# gigatron-expansion-v5.net
KiCad netlist of a schematic drawn in EasyEDA
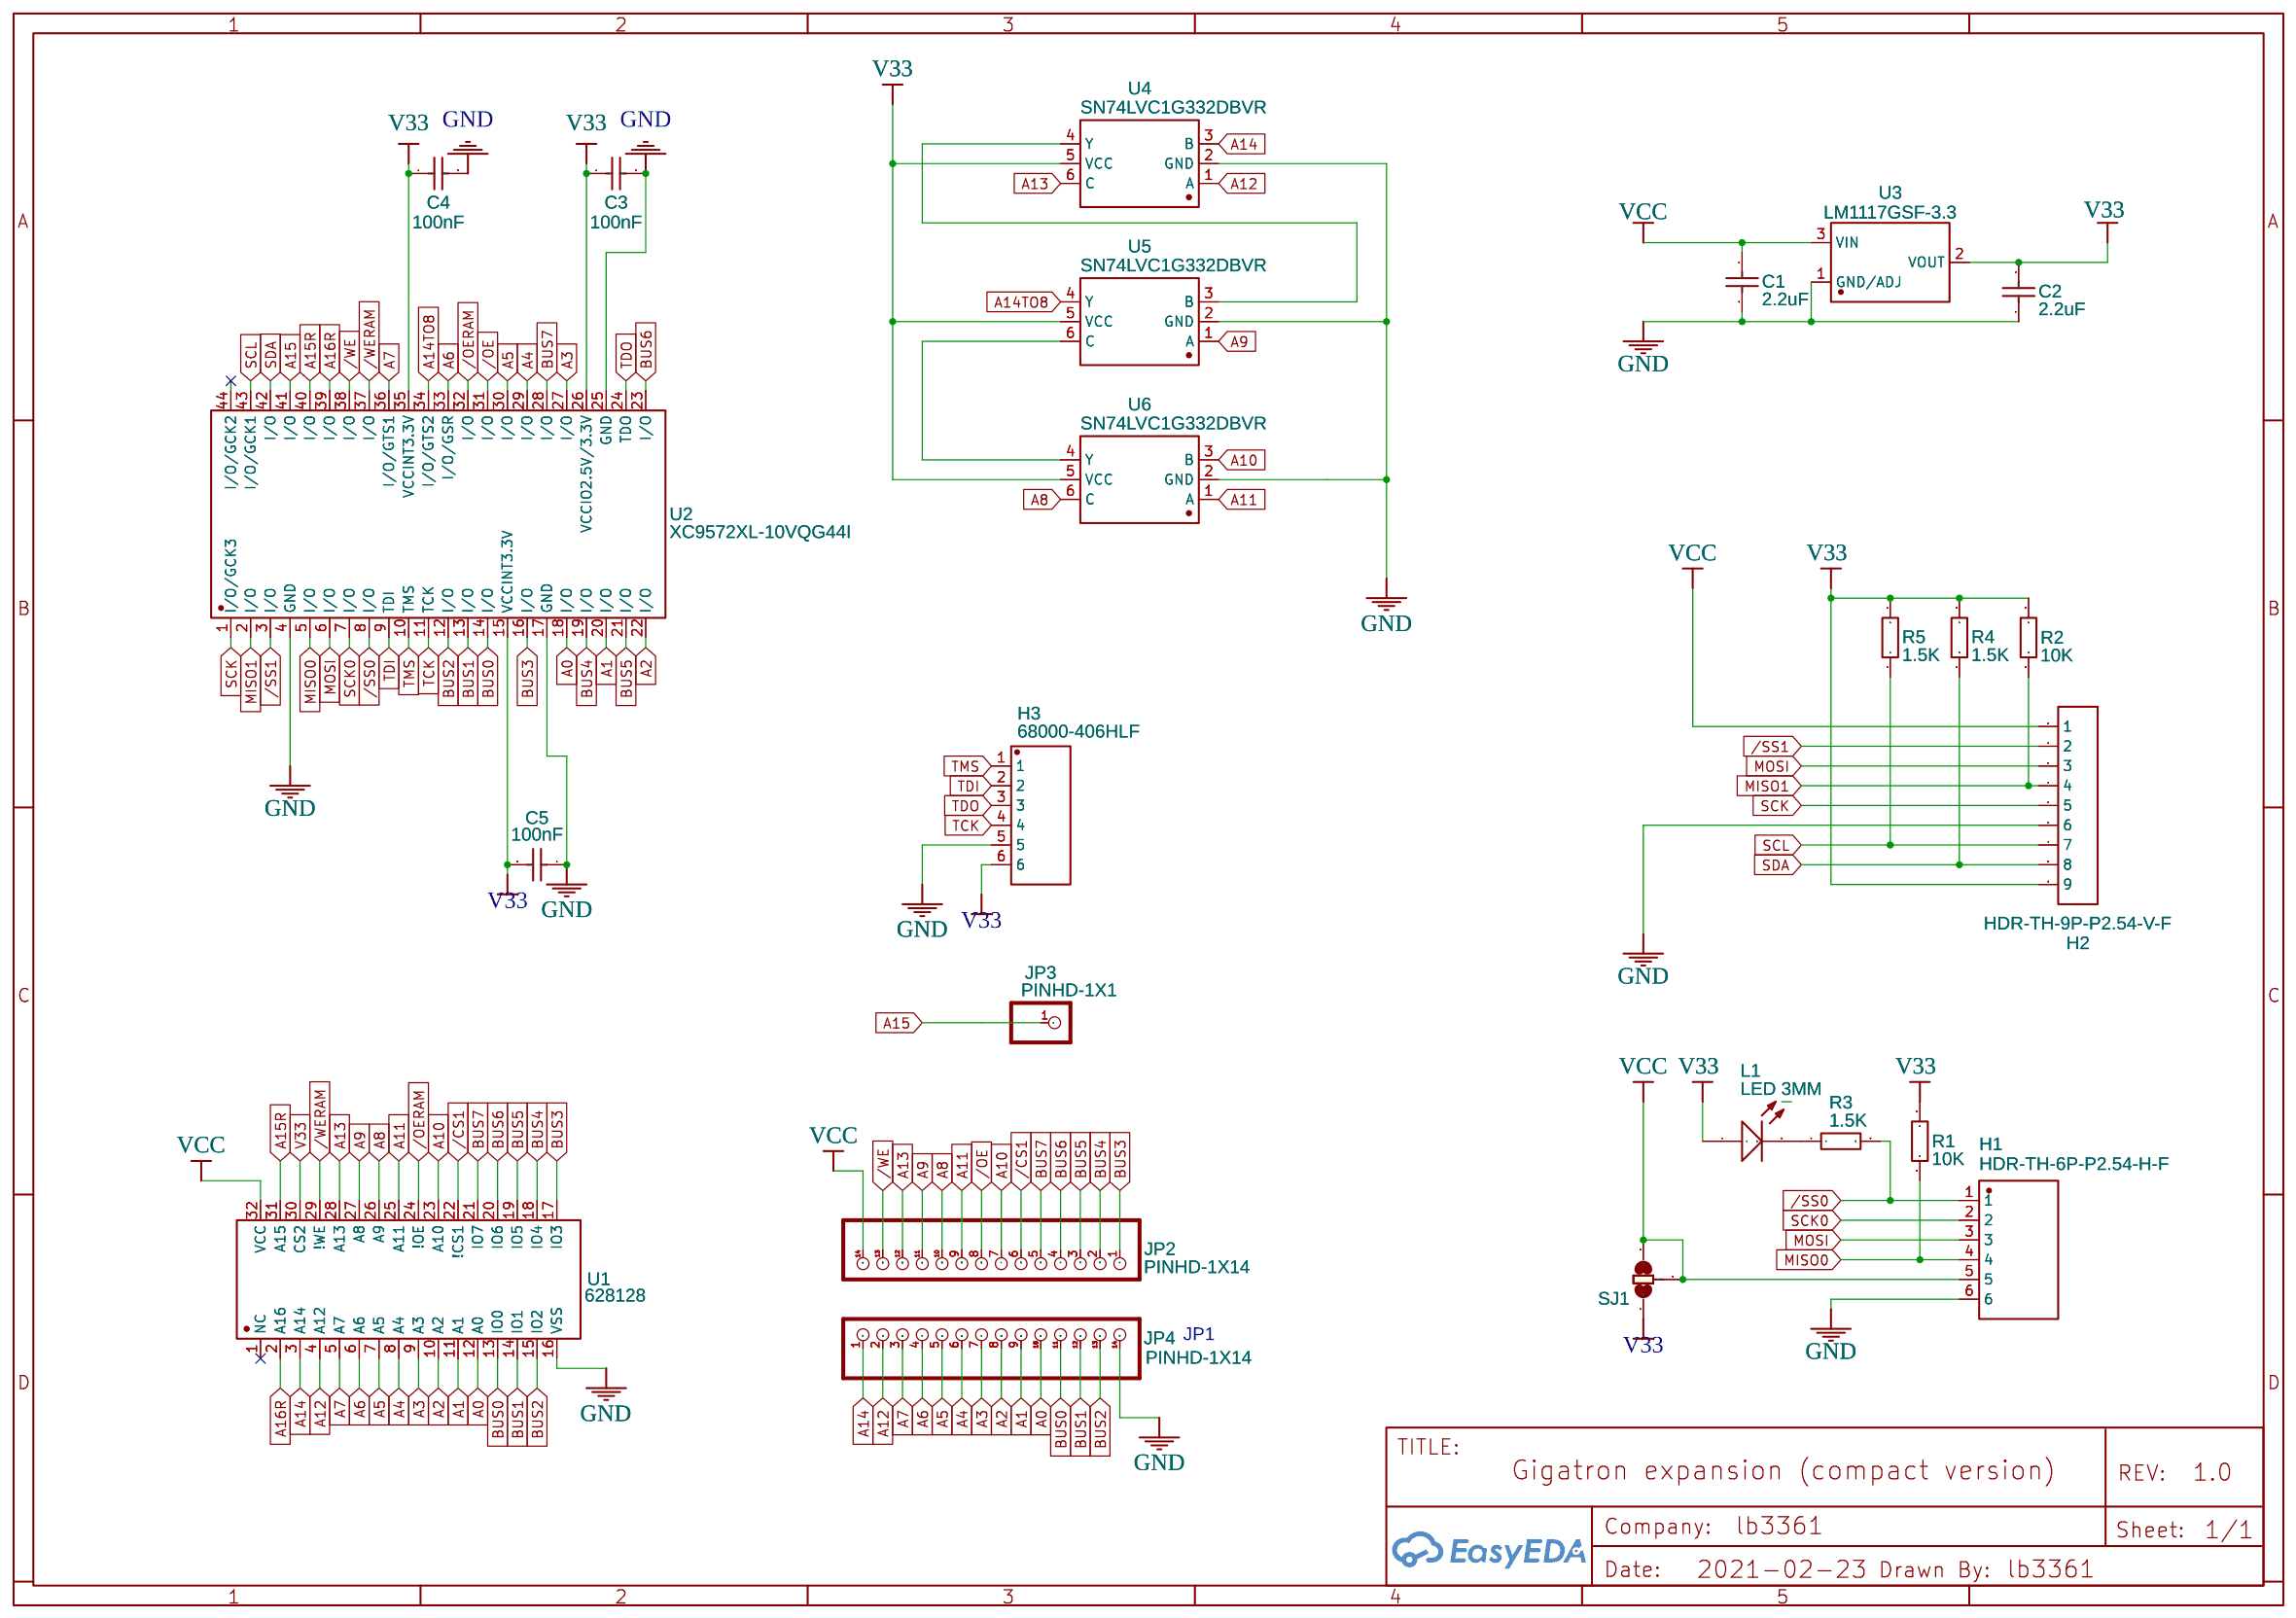
[diagram p0: schematic sheet]

(export (version "E")
  (design (tool "Eeschema 10.0.6"))
  (components
    (comp (ref "C1")
      (value "2.2uF")
      (fields
        (field (name "BOM_Manufacturer Part") "0805F225M500NT")
        (field (name "BOM_Supplier Part") "C49217")
      )
      (libsource (lib "") (part "0805F225M500NT"))
    )
    (comp (ref "C2")
      (value "2.2uF")
      (fields
        (field (name "BOM_Manufacturer Part") "0805F225M500NT")
        (field (name "BOM_Supplier Part") "C49217")
      )
      (libsource (lib "") (part "0805F225M500NT"))
    )
    (comp (ref "C3")
      (value "100nF")
      (fields
        (field (name "BOM_Manufacturer Part") "CL05B104KO5NNNC")
        (field (name "BOM_Supplier Part") "C1525")
      )
      (libsource (lib "") (part "CL05B104KO5NNNC_1"))
    )
    (comp (ref "C4")
      (value "100nF")
      (fields
        (field (name "BOM_Manufacturer Part") "CL05B104KO5NNNC")
        (field (name "BOM_Supplier Part") "C1525")
      )
      (libsource (lib "") (part "CL05B104KO5NNNC_1"))
    )
    (comp (ref "C5")
      (value "100nF")
      (fields
        (field (name "BOM_Manufacturer Part") "CL05B104KO5NNNC")
        (field (name "BOM_Supplier Part") "C1525")
      )
      (libsource (lib "") (part "CL05B104KO5NNNC"))
    )
    (comp (ref "H1")
      (value "HDR-TH-6P-P2.54-H-F")
      (fields
        (field (name "BOM_Manufacturer Part") "A2541HWR-6P")
        (field (name "BOM_Supplier Part") "C225514")
      )
      (libsource (lib "") (part "A2541HWR-6P"))
    )
    (comp (ref "H2")
      (value "HDR-TH-9P-P2.54-V-F")
      (fields
        (field (name "BOM_Manufacturer Part") "2.54mm 1*9 Straight Female header")
        (field (name "BOM_Supplier Part") "C39576")
      )
      (libsource (lib "") (part "Header-Female-2.54_1x9"))
    )
    (comp (ref "H3")
      (value "68000-406HLF")
      (fields (field (name "BOM_Supplier Part") "C178289"))
      (libsource (lib "") (part "68000-406HLF"))
    )
    (comp (ref "JP2") (value "PINHD-1X14") (libsource (lib "") (part "PINHD-1X14_1")))
    (comp (ref "JP3") (value "PINHD-1X1") (libsource (lib "") (part "PINHD-1X1")))
    (comp (ref "JP4") (value "PINHD-1X14") (libsource (lib "") (part "PINHD-1X14")))
    (comp (ref "L1")
      (value "LED 3MM")
      (fields (field (name "BOM_Manufacturer Part") "TSAL4400") (field (name "BOM_Supplier Part") "C94135"))
      (libsource (lib "") (part "TSAL4400"))
    )
    (comp (ref "R1")
      (value "10K")
      (fields
        (field (name "BOM_Manufacturer Part") "0402WGF1002TCE")
        (field (name "BOM_Supplier Part") "C25744")
      )
      (libsource (lib "") (part "0402WGF1002TCE"))
    )
    (comp (ref "R2")
      (value "10K")
      (fields
        (field (name "BOM_Manufacturer Part") "0402WGF1002TCE")
        (field (name "BOM_Supplier Part") "C25744")
      )
      (libsource (lib "") (part "0402WGF1002TCE"))
    )
    (comp (ref "R3")
      (value "1.5K")
      (fields
        (field (name "BOM_Manufacturer Part") "0402WGF1501TCE")
        (field (name "BOM_Supplier Part") "C25867")
      )
      (libsource (lib "") (part "0402WGF1501TCE_1"))
    )
    (comp (ref "R4")
      (value "1.5K")
      (fields
        (field (name "BOM_Manufacturer Part") "0402WGF1501TCE")
        (field (name "BOM_Supplier Part") "C25867")
      )
      (libsource (lib "") (part "0402WGF1501TCE"))
    )
    (comp (ref "R5")
      (value "1.5K")
      (fields
        (field (name "BOM_Manufacturer Part") "0402WGF1501TCE")
        (field (name "BOM_Supplier Part") "C25867")
      )
      (libsource (lib "") (part "0402WGF1501TCE"))
    )
    (comp (ref "SJ1") (value "SOLDERJUMPER_2WAYT") (libsource (lib "") (part "SOLDERJUMPER_2WAYT")))
    (comp (ref "U1") (value "628128") (libsource (lib "") (part "628128P")))
    (comp (ref "U2")
      (value "XC9572XL-10VQG44I")
      (fields (field (name "BOM_Supplier Part") "C96598"))
      (libsource (lib "") (part "XC9572XL-10VQG44I"))
    )
    (comp (ref "U3")
      (value "LM1117GSF-3.3")
      (fields (field (name "BOM_Supplier Part") "C481677"))
      (libsource (lib "") (part "LM1117GSF-3.3"))
    )
    (comp (ref "U4")
      (value "SN74LVC1G332DBVR")
      (fields (field (name "BOM_Supplier Part") "C43368"))
      (libsource (lib "") (part "SN74LVC1G332DBVR"))
    )
    (comp (ref "U5")
      (value "SN74LVC1G332DBVR")
      (fields (field (name "BOM_Supplier Part") "C43368"))
      (libsource (lib "") (part "SN74LVC1G332DBVR"))
    )
    (comp (ref "U6")
      (value "SN74LVC1G332DBVR")
      (fields (field (name "BOM_Supplier Part") "C43368"))
      (libsource (lib "") (part "SN74LVC1G332DBVR"))
    )
  )
  (nets
    (net (code "1") (name "A0") (class "Default")
      (node (ref "JP4") (pin "10") (pinfunction "10_10") (pintype "unspecified"))
      (node (ref "U1") (pin "12") (pinfunction "A0_12") (pintype "unspecified"))
      (node (ref "U2") (pin "18") (pinfunction "I/O_18") (pintype "unspecified"))
    )
    (net (code "2") (name "A1") (class "Default")
      (node (ref "JP4") (pin "9") (pinfunction "9_9") (pintype "unspecified"))
      (node (ref "U1") (pin "11") (pinfunction "A1_11") (pintype "unspecified"))
      (node (ref "U2") (pin "20") (pinfunction "I/O_20") (pintype "unspecified"))
    )
    (net (code "3") (name "A2") (class "Default")
      (node (ref "JP4") (pin "8") (pinfunction "8_8") (pintype "unspecified"))
      (node (ref "U1") (pin "10") (pinfunction "A2_10") (pintype "unspecified"))
      (node (ref "U2") (pin "22") (pinfunction "I/O_22") (pintype "unspecified"))
    )
    (net (code "4") (name "A3") (class "Default")
      (node (ref "JP4") (pin "7") (pinfunction "7_7") (pintype "unspecified"))
      (node (ref "U1") (pin "9") (pinfunction "A3_9") (pintype "unspecified"))
      (node (ref "U2") (pin "27") (pinfunction "I/O_27") (pintype "unspecified"))
    )
    (net (code "5") (name "A4") (class "Default")
      (node (ref "JP4") (pin "6") (pinfunction "6_6") (pintype "unspecified"))
      (node (ref "U1") (pin "8") (pinfunction "A4_8") (pintype "unspecified"))
      (node (ref "U2") (pin "29") (pinfunction "I/O_29") (pintype "unspecified"))
    )
    (net (code "6") (name "A5") (class "Default")
      (node (ref "JP4") (pin "5") (pinfunction "5_5") (pintype "unspecified"))
      (node (ref "U1") (pin "7") (pinfunction "A5_7") (pintype "unspecified"))
      (node (ref "U2") (pin "30") (pinfunction "I/O_30") (pintype "unspecified"))
    )
    (net (code "7") (name "A6") (class "Default")
      (node (ref "JP4") (pin "4") (pinfunction "4_4") (pintype "unspecified"))
      (node (ref "U1") (pin "6") (pinfunction "A6_6") (pintype "unspecified"))
      (node (ref "U2") (pin "33") (pinfunction "I/O/GSR_33") (pintype "unspecified"))
    )
    (net (code "8") (name "A7") (class "Default")
      (node (ref "JP4") (pin "3") (pinfunction "3_3") (pintype "unspecified"))
      (node (ref "U1") (pin "5") (pinfunction "A7_5") (pintype "unspecified"))
      (node (ref "U2") (pin "36") (pinfunction "I/O/GTS1_36") (pintype "unspecified"))
    )
    (net (code "9") (name "A8") (class "Default")
      (node (ref "JP2") (pin "10") (pinfunction "10_10") (pintype "unspecified"))
      (node (ref "U1") (pin "26") (pinfunction "A9_26") (pintype "unspecified"))
      (node (ref "U6") (pin "6") (pinfunction "C_6") (pintype "unspecified"))
    )
    (net (code "10") (name "A9") (class "Default")
      (node (ref "JP2") (pin "11") (pinfunction "11_11") (pintype "unspecified"))
      (node (ref "U1") (pin "27") (pinfunction "A8_27") (pintype "unspecified"))
      (node (ref "U5") (pin "1") (pinfunction "A_1") (pintype "unspecified"))
    )
    (net (code "11") (name "A10") (class "Default")
      (node (ref "JP2") (pin "7") (pinfunction "7_7") (pintype "unspecified"))
      (node (ref "U1") (pin "23") (pinfunction "A10_23") (pintype "unspecified"))
      (node (ref "U6") (pin "3") (pinfunction "B_3") (pintype "unspecified"))
    )
    (net (code "12") (name "A11") (class "Default")
      (node (ref "JP2") (pin "9") (pinfunction "9_9") (pintype "unspecified"))
      (node (ref "U1") (pin "25") (pinfunction "A11_25") (pintype "unspecified"))
      (node (ref "U6") (pin "1") (pinfunction "A_1") (pintype "unspecified"))
    )
    (net (code "13") (name "A12") (class "Default")
      (node (ref "JP4") (pin "2") (pinfunction "2_2") (pintype "unspecified"))
      (node (ref "U1") (pin "4") (pinfunction "A12_4") (pintype "unspecified"))
      (node (ref "U4") (pin "1") (pinfunction "A_1") (pintype "unspecified"))
    )
    (net (code "14") (name "A13") (class "Default")
      (node (ref "JP2") (pin "12") (pinfunction "12_12") (pintype "unspecified"))
      (node (ref "U1") (pin "28") (pinfunction "A13_28") (pintype "unspecified"))
      (node (ref "U4") (pin "6") (pinfunction "C_6") (pintype "unspecified"))
    )
    (net (code "15") (name "A14") (class "Default")
      (node (ref "JP4") (pin "1") (pinfunction "1_1") (pintype "unspecified"))
      (node (ref "U1") (pin "3") (pinfunction "A14_3") (pintype "unspecified"))
      (node (ref "U4") (pin "3") (pinfunction "B_3") (pintype "unspecified"))
    )
    (net (code "16") (name "A14TO8") (class "Default")
      (node (ref "U2") (pin "34") (pinfunction "I/O/GTS2_34") (pintype "unspecified"))
      (node (ref "U5") (pin "4") (pinfunction "Y_4") (pintype "unspecified"))
    )
    (net (code "17") (name "A15") (class "Default")
      (node (ref "JP3") (pin "1") (pinfunction "1_1") (pintype "unspecified"))
      (node (ref "U2") (pin "41") (pinfunction "I/O_41") (pintype "unspecified"))
    )
    (net (code "18") (name "A15R") (class "Default")
      (node (ref "U1") (pin "31") (pinfunction "A15_31") (pintype "unspecified"))
      (node (ref "U2") (pin "40") (pinfunction "I/O_40") (pintype "unspecified"))
    )
    (net (code "19") (name "A16R") (class "Default")
      (node (ref "U1") (pin "2") (pinfunction "A16_2") (pintype "unspecified"))
      (node (ref "U2") (pin "39") (pinfunction "I/O_39") (pintype "unspecified"))
    )
    (net (code "20") (name "BUS0") (class "Default")
      (node (ref "JP4") (pin "11") (pinfunction "11_11") (pintype "unspecified"))
      (node (ref "U1") (pin "13") (pinfunction "IO0_13") (pintype "unspecified"))
      (node (ref "U2") (pin "14") (pinfunction "I/O_14") (pintype "unspecified"))
    )
    (net (code "21") (name "BUS1") (class "Default")
      (node (ref "JP4") (pin "12") (pinfunction "12_12") (pintype "unspecified"))
      (node (ref "U1") (pin "14") (pinfunction "IO1_14") (pintype "unspecified"))
      (node (ref "U2") (pin "13") (pinfunction "I/O_13") (pintype "unspecified"))
    )
    (net (code "22") (name "BUS2") (class "Default")
      (node (ref "JP4") (pin "13") (pinfunction "13_13") (pintype "unspecified"))
      (node (ref "U1") (pin "15") (pinfunction "IO2_15") (pintype "unspecified"))
      (node (ref "U2") (pin "12") (pinfunction "I/O_12") (pintype "unspecified"))
    )
    (net (code "23") (name "BUS3") (class "Default")
      (node (ref "JP2") (pin "1") (pinfunction "1_1") (pintype "unspecified"))
      (node (ref "U1") (pin "17") (pinfunction "IO3_17") (pintype "unspecified"))
      (node (ref "U2") (pin "16") (pinfunction "I/O_16") (pintype "unspecified"))
    )
    (net (code "24") (name "BUS4") (class "Default")
      (node (ref "JP2") (pin "2") (pinfunction "2_2") (pintype "unspecified"))
      (node (ref "U1") (pin "18") (pinfunction "IO4_18") (pintype "unspecified"))
      (node (ref "U2") (pin "19") (pinfunction "I/O_19") (pintype "unspecified"))
    )
    (net (code "25") (name "BUS5") (class "Default")
      (node (ref "JP2") (pin "3") (pinfunction "3_3") (pintype "unspecified"))
      (node (ref "U1") (pin "19") (pinfunction "IO5_19") (pintype "unspecified"))
      (node (ref "U2") (pin "21") (pinfunction "I/O_21") (pintype "unspecified"))
    )
    (net (code "26") (name "BUS6") (class "Default")
      (node (ref "JP2") (pin "4") (pinfunction "4_4") (pintype "unspecified"))
      (node (ref "U1") (pin "20") (pinfunction "IO6_20") (pintype "unspecified"))
      (node (ref "U2") (pin "23") (pinfunction "I/O_23") (pintype "unspecified"))
    )
    (net (code "27") (name "BUS7") (class "Default")
      (node (ref "JP2") (pin "5") (pinfunction "5_5") (pintype "unspecified"))
      (node (ref "U1") (pin "21") (pinfunction "IO7_21") (pintype "unspecified"))
      (node (ref "U2") (pin "28") (pinfunction "I/O_28") (pintype "unspecified"))
    )
    (net (code "28") (name "GND") (class "Default")
      (node (ref "C1") (pin "2") (pinfunction "2_2") (pintype "input"))
      (node (ref "C2") (pin "2") (pinfunction "2_2") (pintype "input"))
      (node (ref "C3") (pin "2") (pinfunction "2_2") (pintype "input"))
      (node (ref "C4") (pin "2") (pinfunction "2_2") (pintype "input"))
      (node (ref "C5") (pin "1") (pinfunction "1_1") (pintype "input"))
      (node (ref "H1") (pin "6") (pinfunction "6_6") (pintype "unspecified"))
      (node (ref "H2") (pin "6") (pinfunction "6_6") (pintype "input"))
      (node (ref "H3") (pin "5") (pinfunction "5_5") (pintype "unspecified"))
      (node (ref "JP4") (pin "14") (pinfunction "14_14") (pintype "unspecified"))
      (node (ref "U1") (pin "16") (pinfunction "VSS_16") (pintype "unspecified"))
      (node (ref "U2") (pin "17") (pinfunction "GND_17") (pintype "unspecified"))
      (node (ref "U2") (pin "25") (pinfunction "GND_25") (pintype "unspecified"))
      (node (ref "U2") (pin "4") (pinfunction "GND_4") (pintype "unspecified"))
      (node (ref "U3") (pin "1") (pinfunction "GND/ADJ_1") (pintype "unspecified"))
      (node (ref "U4") (pin "2") (pinfunction "GND_2") (pintype "unspecified"))
      (node (ref "U5") (pin "2") (pinfunction "GND_2") (pintype "unspecified"))
      (node (ref "U6") (pin "2") (pinfunction "GND_2") (pintype "unspecified"))
    )
    (net (code "29") (name "MISO0") (class "Default")
      (node (ref "H1") (pin "4") (pinfunction "4_4") (pintype "unspecified"))
      (node (ref "R1") (pin "1") (pinfunction "1_1") (pintype "input"))
      (node (ref "U2") (pin "5") (pinfunction "I/O_5") (pintype "unspecified"))
    )
    (net (code "30") (name "MISO1") (class "Default")
      (node (ref "H2") (pin "4") (pinfunction "4_4") (pintype "input"))
      (node (ref "R2") (pin "1") (pinfunction "1_1") (pintype "input"))
      (node (ref "U2") (pin "2") (pinfunction "I/O_2") (pintype "unspecified"))
    )
    (net (code "31") (name "MOSI") (class "Default")
      (node (ref "H1") (pin "3") (pinfunction "3_3") (pintype "unspecified"))
      (node (ref "H2") (pin "3") (pinfunction "3_3") (pintype "input"))
      (node (ref "U2") (pin "6") (pinfunction "I/O_6") (pintype "unspecified"))
    )
    (net (code "32") (name "Net-(L1-C)") (class "Default")
      (node (ref "L1") (pin "2") (pinfunction "C_2") (pintype "input"))
      (node (ref "R3") (pin "1") (pinfunction "1_1") (pintype "input"))
    )
    (net (code "33") (name "Net-(U4-Y)") (class "Default")
      (node (ref "U4") (pin "4") (pinfunction "Y_4") (pintype "unspecified"))
      (node (ref "U5") (pin "3") (pinfunction "B_3") (pintype "unspecified"))
    )
    (net (code "34") (name "Net-(U5-C)") (class "Default")
      (node (ref "U5") (pin "6") (pinfunction "C_6") (pintype "unspecified"))
      (node (ref "U6") (pin "4") (pinfunction "Y_4") (pintype "unspecified"))
    )
    (net (code "35") (name "SCK") (class "Default")
      (node (ref "H2") (pin "5") (pinfunction "5_5") (pintype "input"))
      (node (ref "U2") (pin "1") (pinfunction "I/O/GCK3_1") (pintype "unspecified"))
    )
    (net (code "36") (name "SCK0") (class "Default")
      (node (ref "H1") (pin "2") (pinfunction "2_2") (pintype "unspecified"))
      (node (ref "U2") (pin "7") (pinfunction "I/O_7") (pintype "unspecified"))
    )
    (net (code "37") (name "SCL") (class "Default")
      (node (ref "H2") (pin "7") (pinfunction "7_7") (pintype "input"))
      (node (ref "R5") (pin "1") (pinfunction "1_1") (pintype "input"))
      (node (ref "U2") (pin "43") (pinfunction "I/O/GCK1_43") (pintype "unspecified"))
    )
    (net (code "38") (name "SDA") (class "Default")
      (node (ref "H2") (pin "8") (pinfunction "8_8") (pintype "input"))
      (node (ref "R4") (pin "1") (pinfunction "1_1") (pintype "input"))
      (node (ref "U2") (pin "42") (pinfunction "I/O_42") (pintype "unspecified"))
    )
    (net (code "39") (name "TCK") (class "Default")
      (node (ref "H3") (pin "4") (pinfunction "4_4") (pintype "unspecified"))
      (node (ref "U2") (pin "11") (pinfunction "TCK_11") (pintype "unspecified"))
    )
    (net (code "40") (name "TDI") (class "Default")
      (node (ref "H3") (pin "2") (pinfunction "2_2") (pintype "unspecified"))
      (node (ref "U2") (pin "9") (pinfunction "TDI_9") (pintype "unspecified"))
    )
    (net (code "41") (name "TDO") (class "Default")
      (node (ref "H3") (pin "3") (pinfunction "3_3") (pintype "unspecified"))
      (node (ref "U2") (pin "24") (pinfunction "TDO_24") (pintype "unspecified"))
    )
    (net (code "42") (name "TMS") (class "Default")
      (node (ref "H3") (pin "1") (pinfunction "1_1") (pintype "unspecified"))
      (node (ref "U2") (pin "10") (pinfunction "TMS_10") (pintype "unspecified"))
    )
    (net (code "43") (name "V33") (class "Default")
      (node (ref "C2") (pin "1") (pinfunction "1_1") (pintype "input"))
      (node (ref "C3") (pin "1") (pinfunction "1_1") (pintype "input"))
      (node (ref "C4") (pin "1") (pinfunction "1_1") (pintype "input"))
      (node (ref "C5") (pin "2") (pinfunction "2_2") (pintype "input"))
      (node (ref "H2") (pin "9") (pinfunction "9_9") (pintype "input"))
      (node (ref "H3") (pin "6") (pinfunction "6_6") (pintype "unspecified"))
      (node (ref "L1") (pin "1") (pinfunction "A_1") (pintype "input"))
      (node (ref "R1") (pin "2") (pinfunction "2_2") (pintype "input"))
      (node (ref "R2") (pin "2") (pinfunction "2_2") (pintype "input"))
      (node (ref "R4") (pin "2") (pinfunction "2_2") (pintype "input"))
      (node (ref "R5") (pin "2") (pinfunction "2_2") (pintype "input"))
      (node (ref "SJ1") (pin "1") (pinfunction "1_1") (pintype "unspecified"))
      (node (ref "U1") (pin "30") (pinfunction "CS2_30") (pintype "unspecified"))
      (node (ref "U2") (pin "15") (pinfunction "VCCINT3.3V_15") (pintype "unspecified"))
      (node (ref "U2") (pin "26") (pinfunction "VCCIO2.5V/3.3V_26") (pintype "unspecified"))
      (node (ref "U2") (pin "35") (pinfunction "VCCINT3.3V_35") (pintype "unspecified"))
      (node (ref "U3") (pin "2") (pinfunction "VOUT_2") (pintype "unspecified"))
      (node (ref "U4") (pin "5") (pinfunction "VCC_5") (pintype "unspecified"))
      (node (ref "U5") (pin "5") (pinfunction "VCC_5") (pintype "unspecified"))
      (node (ref "U6") (pin "5") (pinfunction "VCC_5") (pintype "unspecified"))
    )
    (net (code "44") (name "VCC") (class "Default")
      (node (ref "C1") (pin "1") (pinfunction "1_1") (pintype "input"))
      (node (ref "H1") (pin "5") (pinfunction "5_5") (pintype "unspecified"))
      (node (ref "H2") (pin "1") (pinfunction "1_1") (pintype "input"))
      (node (ref "JP2") (pin "14") (pinfunction "14_14") (pintype "unspecified"))
      (node (ref "SJ1") (pin "2") (pinfunction "2_2") (pintype "unspecified"))
      (node (ref "SJ1") (pin "3") (pinfunction "3_3") (pintype "unspecified"))
      (node (ref "U1") (pin "32") (pinfunction "VCC_32") (pintype "unspecified"))
      (node (ref "U3") (pin "3") (pinfunction "VIN_3") (pintype "unspecified"))
    )
    (net (code "45") (name "unconnected-(U1-NC-Pad1)") (class "Default")
      (node (ref "U1") (pin "1") (pinfunction "NC_1") (pintype "unspecified+no_connect"))
    )
    (net (code "46") (name "unconnected-(U2-I{slash}O{slash}GCK2-Pad44)") (class "Default")
      (node (ref "U2") (pin "44") (pinfunction "I/O/GCK2_44") (pintype "unspecified+no_connect"))
    )
    (net (code "47") (name "{slash}CS1") (class "Default")
      (node (ref "JP2") (pin "6") (pinfunction "6_6") (pintype "unspecified"))
      (node (ref "U1") (pin "22") (pinfunction "!CS1_22") (pintype "unspecified"))
    )
    (net (code "48") (name "{slash}OE") (class "Default")
      (node (ref "JP2") (pin "8") (pinfunction "8_8") (pintype "unspecified"))
      (node (ref "U2") (pin "31") (pinfunction "I/O_31") (pintype "unspecified"))
    )
    (net (code "49") (name "{slash}OERAM") (class "Default")
      (node (ref "U1") (pin "24") (pinfunction "!OE_24") (pintype "unspecified"))
      (node (ref "U2") (pin "32") (pinfunction "I/O_32") (pintype "unspecified"))
    )
    (net (code "50") (name "{slash}SS0") (class "Default")
      (node (ref "H1") (pin "1") (pinfunction "1_1") (pintype "unspecified"))
      (node (ref "R3") (pin "2") (pinfunction "2_2") (pintype "input"))
      (node (ref "U2") (pin "8") (pinfunction "I/O_8") (pintype "unspecified"))
    )
    (net (code "51") (name "{slash}SS1") (class "Default")
      (node (ref "H2") (pin "2") (pinfunction "2_2") (pintype "input"))
      (node (ref "U2") (pin "3") (pinfunction "I/O_3") (pintype "unspecified"))
    )
    (net (code "52") (name "{slash}WE") (class "Default")
      (node (ref "JP2") (pin "13") (pinfunction "13_13") (pintype "unspecified"))
      (node (ref "U2") (pin "38") (pinfunction "I/O_38") (pintype "unspecified"))
    )
    (net (code "53") (name "{slash}WERAM") (class "Default")
      (node (ref "U1") (pin "29") (pinfunction "!WE_29") (pintype "unspecified"))
      (node (ref "U2") (pin "37") (pinfunction "I/O_37") (pintype "unspecified"))
    )
  )
)
